# design.net
KiCad netlist of a schematic drawn in EasyEDA Pro
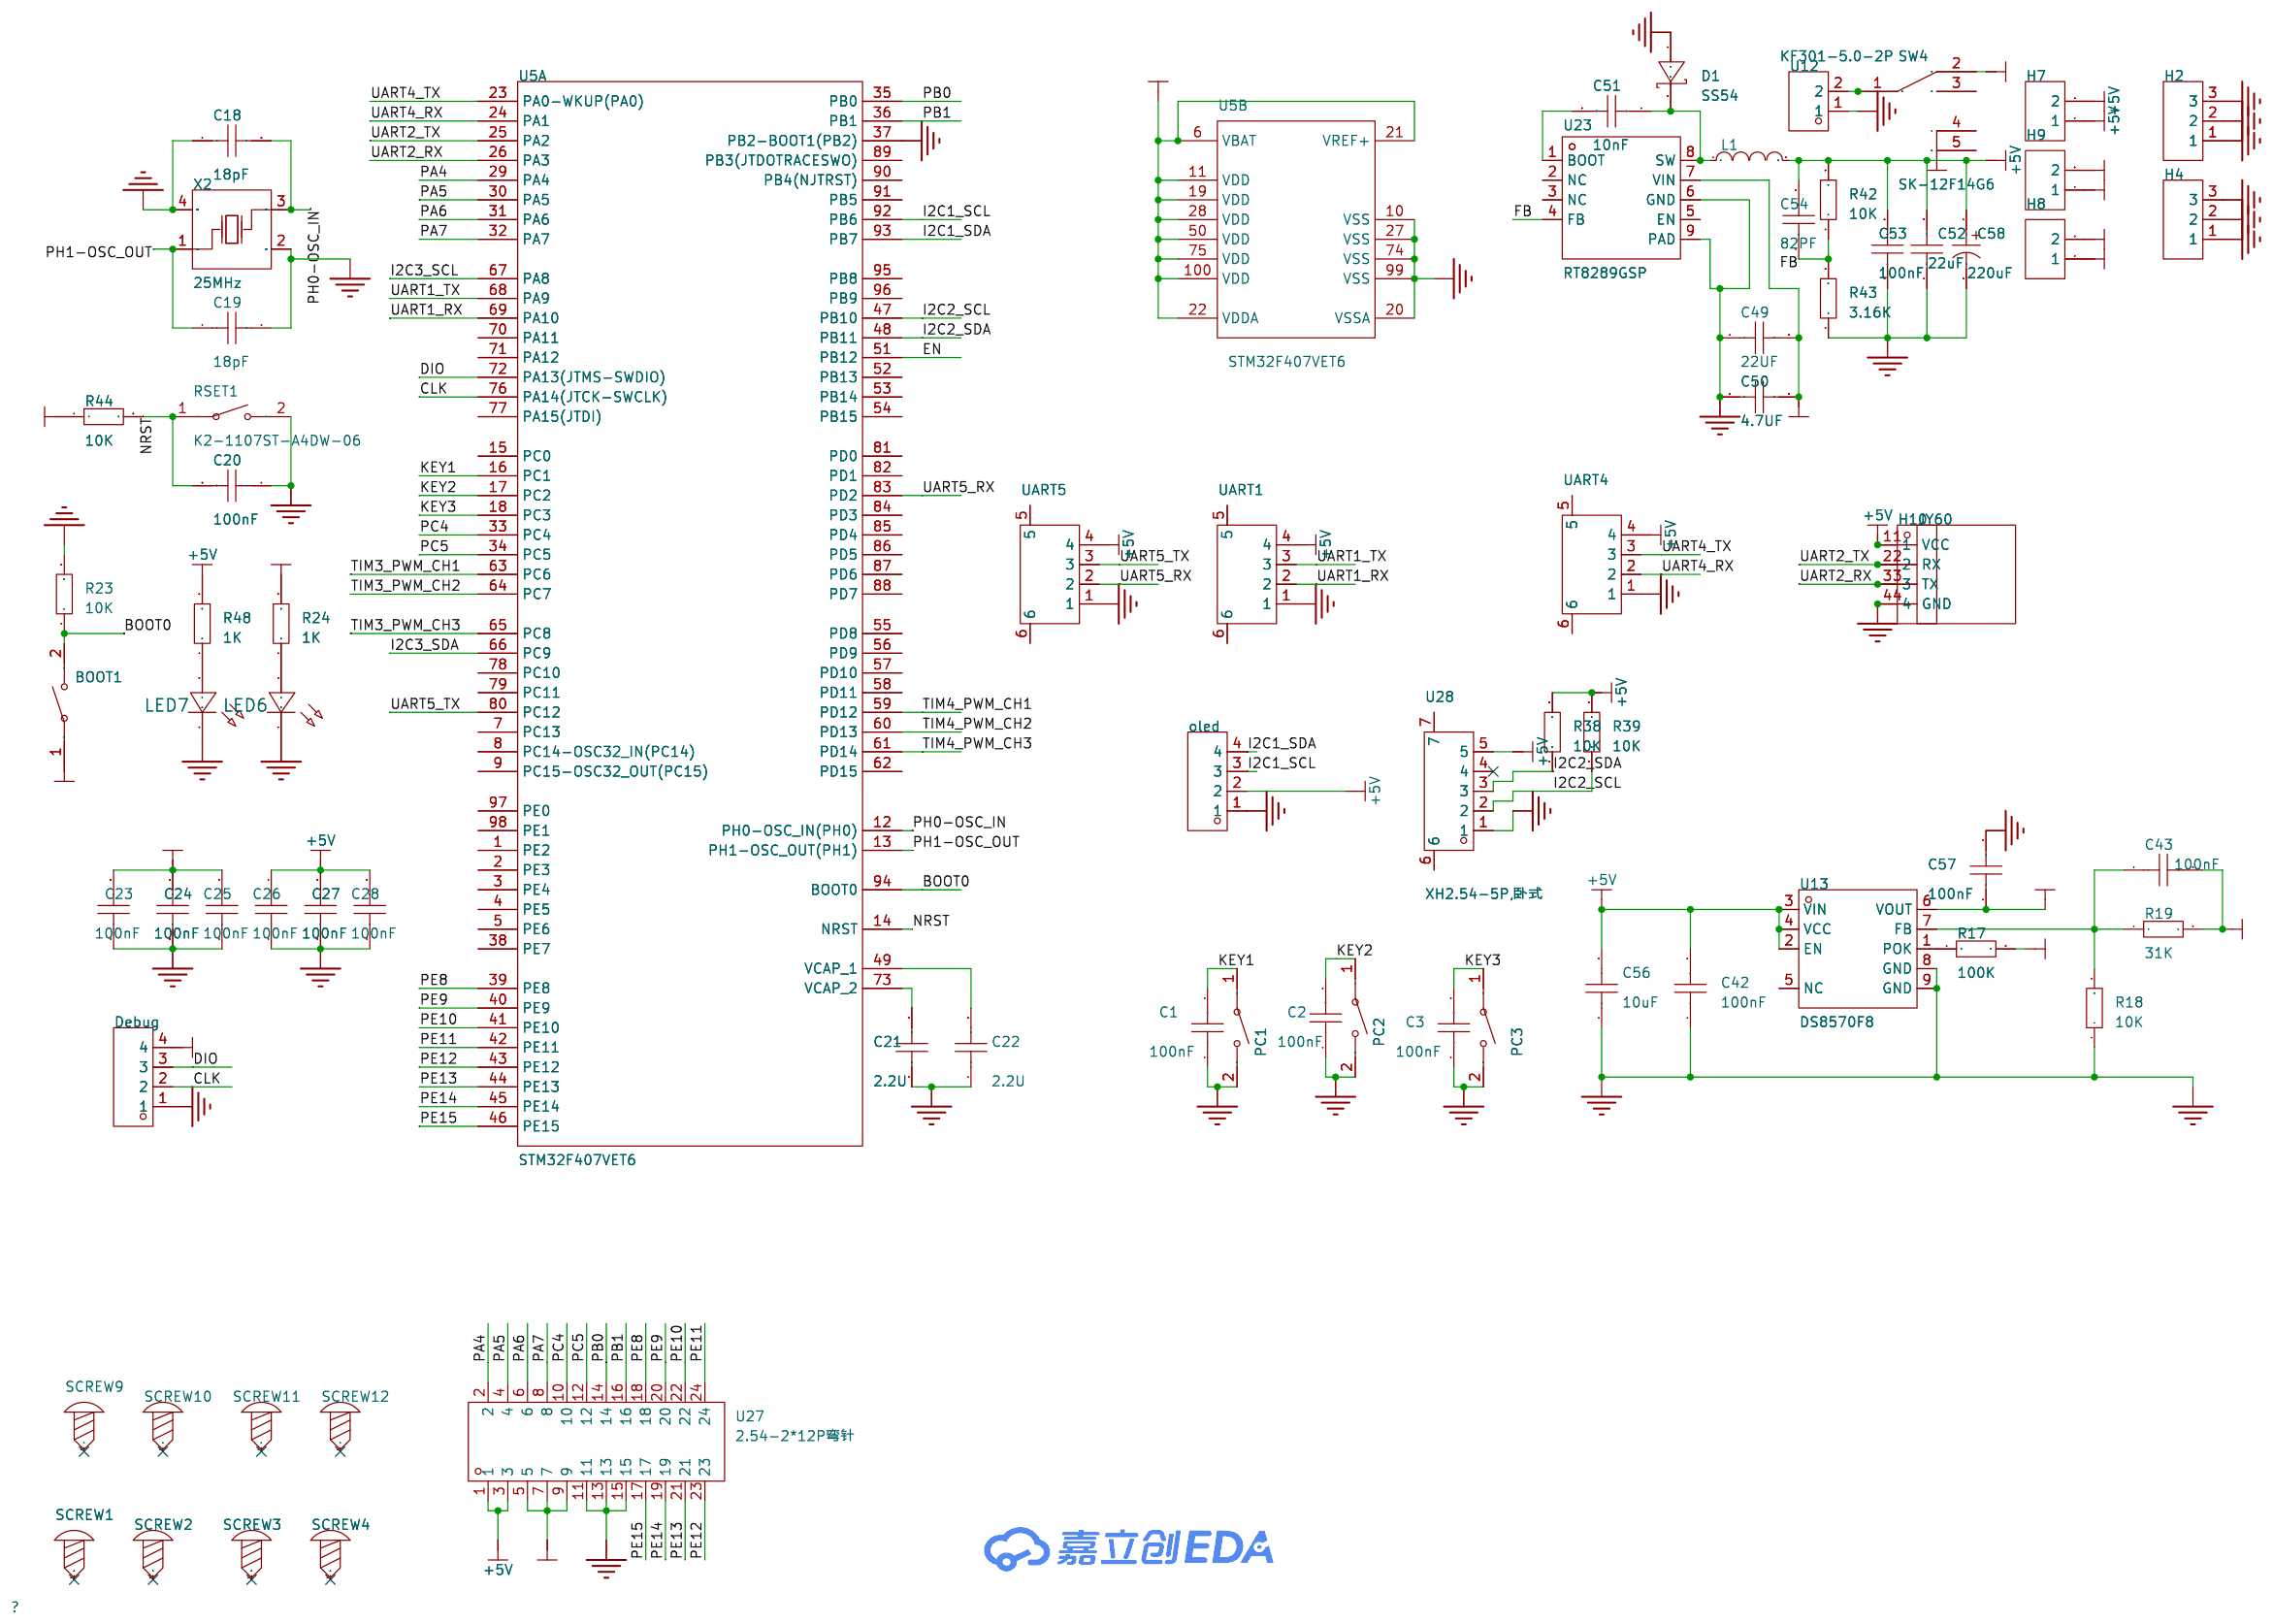
[diagram p0: 主控]
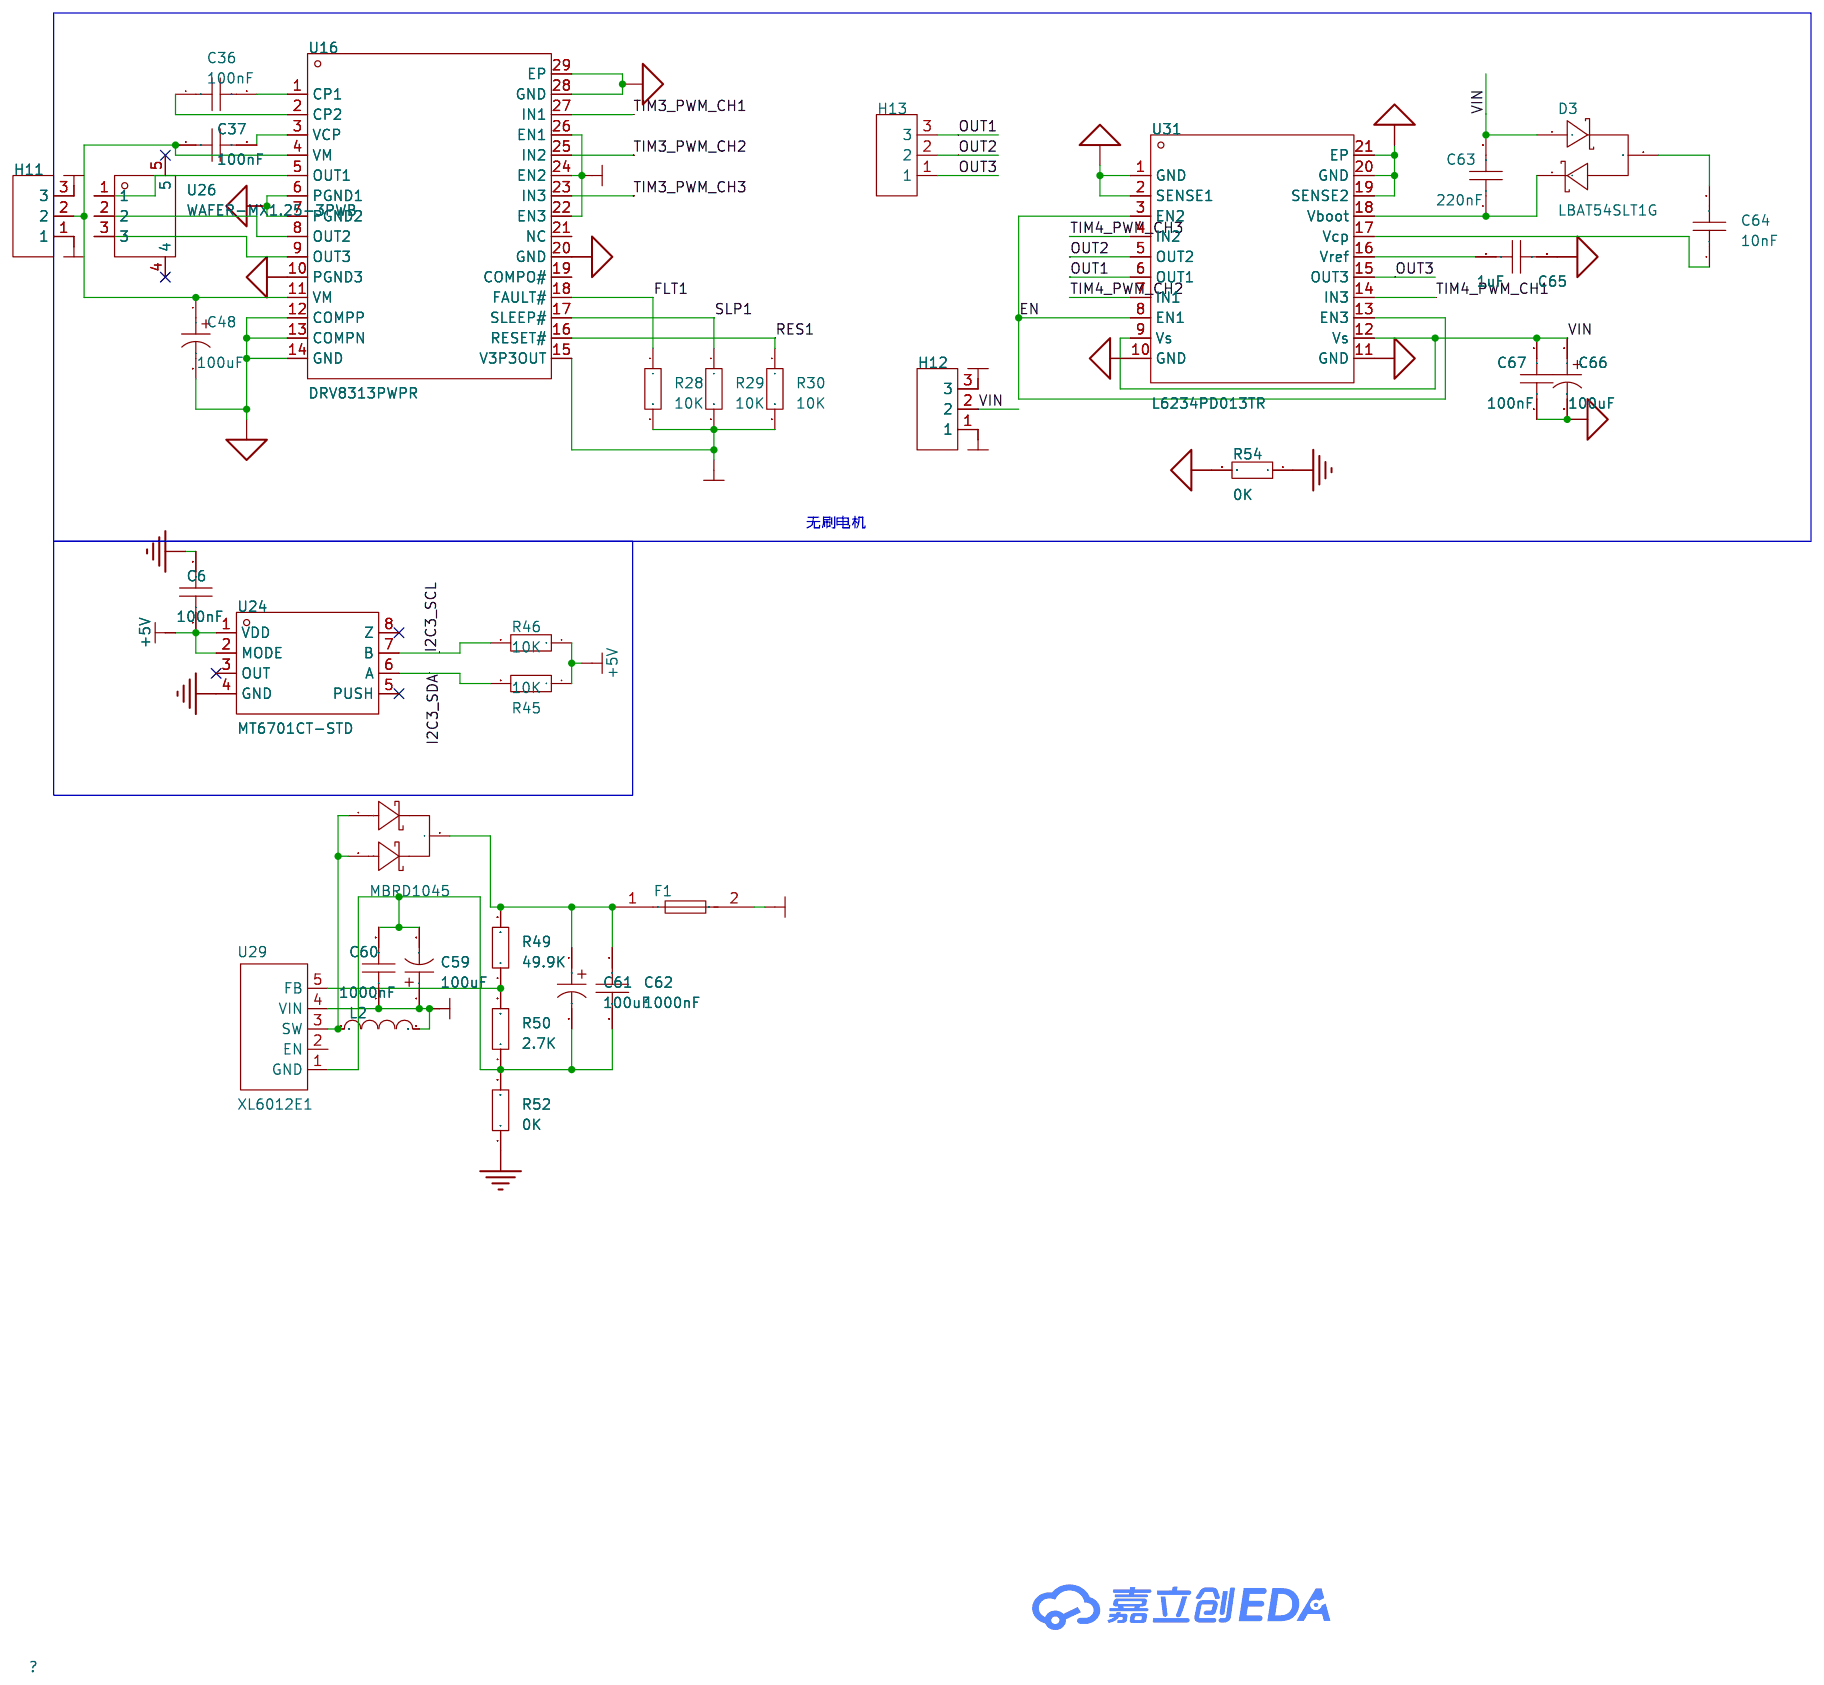
[diagram p1: 驱动]

(export (version "E")
  (design (tool "Eeschema 10.0.6"))
  (components
    (comp (ref "BOOT1")
      (value "K2-1107ST-A4DW-06")
      (footprint "easyedapro:KEY-SMD_L6.2-W3.6-LS8.0")
      (fields (field (name "Manufacturer") "韩国韩荣"))
      (libsource (lib "easyedapro") (part "K2-1107ST-A4SW-06"))
    )
    (comp (ref "C1")
      (value "100nF")
      (footprint "easyedapro:C0805")
      (libsource (lib "easyedapro") (part "CapAcitance"))
    )
    (comp (ref "C2")
      (value "100nF")
      (footprint "easyedapro:C0805")
      (libsource (lib "easyedapro") (part "CapAcitance"))
    )
    (comp (ref "C3")
      (value "100nF")
      (footprint "easyedapro:C0805")
      (libsource (lib "easyedapro") (part "CapAcitance"))
    )
    (comp (ref "C18")
      (value "18pF")
      (footprint "easyedapro:C0805")
      (libsource (lib "easyedapro") (part "CapAcitance"))
    )
    (comp (ref "C19")
      (value "18pF")
      (footprint "easyedapro:C0805")
      (libsource (lib "easyedapro") (part "CapAcitance"))
    )
    (comp (ref "C20")
      (value "100nF")
      (footprint "easyedapro:C0805")
      (libsource (lib "easyedapro") (part "CapAcitance"))
    )
    (comp (ref "C21")
      (value "2.2U")
      (footprint "easyedapro:C0805")
      (libsource (lib "easyedapro") (part "CapAcitance"))
    )
    (comp (ref "C22")
      (value "2.2U")
      (footprint "easyedapro:C0805")
      (libsource (lib "easyedapro") (part "CapAcitance"))
    )
    (comp (ref "C23")
      (value "100nF")
      (footprint "easyedapro:C0603")
      (libsource (lib "easyedapro") (part "CapAcitance"))
    )
    (comp (ref "C24")
      (value "100nF")
      (footprint "easyedapro:C0603")
      (libsource (lib "easyedapro") (part "CapAcitance"))
    )
    (comp (ref "C25")
      (value "100nF")
      (footprint "easyedapro:C0603")
      (libsource (lib "easyedapro") (part "CapAcitance"))
    )
    (comp (ref "C26")
      (value "100nF")
      (footprint "easyedapro:C0603")
      (libsource (lib "easyedapro") (part "CapAcitance"))
    )
    (comp (ref "C27")
      (value "100nF")
      (footprint "easyedapro:C0603")
      (libsource (lib "easyedapro") (part "CapAcitance"))
    )
    (comp (ref "C28")
      (value "100nF")
      (footprint "easyedapro:C0603")
      (libsource (lib "easyedapro") (part "CapAcitance"))
    )
    (comp (ref "C42")
      (value "100nF")
      (footprint "easyedapro:C0805")
      (libsource (lib "easyedapro") (part "CapAcitance"))
    )
    (comp (ref "C43")
      (value "100nF")
      (footprint "easyedapro:C0805")
      (libsource (lib "easyedapro") (part "CapAcitance"))
    )
    (comp (ref "C49")
      (value "22UF")
      (footprint "easyedapro:C0805")
      (libsource (lib "easyedapro") (part "CapAcitance"))
    )
    (comp (ref "C50")
      (value "4.7UF")
      (footprint "easyedapro:C0805")
      (libsource (lib "easyedapro") (part "CapAcitance"))
    )
    (comp (ref "C51")
      (value "10nF")
      (footprint "easyedapro:C0805")
      (libsource (lib "easyedapro") (part "CapAcitance"))
    )
    (comp (ref "C52")
      (value "22uF")
      (footprint "easyedapro:C0805")
      (libsource (lib "easyedapro") (part "CapAcitance"))
    )
    (comp (ref "C53")
      (value "100nF")
      (footprint "easyedapro:C0805")
      (libsource (lib "easyedapro") (part "CapAcitance"))
    )
    (comp (ref "C54")
      (value "82PF")
      (footprint "easyedapro:C0805")
      (libsource (lib "easyedapro") (part "CapAcitance"))
    )
    (comp (ref "C56")
      (value "10uF")
      (footprint "easyedapro:C0805")
      (libsource (lib "easyedapro") (part "CapAcitance"))
    )
    (comp (ref "C57")
      (value "100nF")
      (footprint "easyedapro:C0603")
      (libsource (lib "easyedapro") (part "CapAcitance"))
    )
    (comp (ref "C58")
      (value "220uF")
      (footprint "easyedapro:CAP-SMD_BD6.3-L6.6-W6.6-FD")
      (description "容值:100uF;精度:±20%;额定电压:35V;")
      (fields (field (name "Manufacturer Part") "VPXC0851V101MVTM") (field (name "Manufacturer") "Ymin(永铭)"))
      (libsource (lib "easyedapro") (part "VPXC0851V101MVTM"))
    )
    (comp (ref "D1")
      (value "SS54")
      (footprint "easyedapro:SMA_L4.4-W2.8-LS5.4-R-RD")
      (description "二极管配置:独立式;正向压降(Vf):550mV@5A;直流反向耐压(Vr):40V;整流电流:5A;")
      (fields (field (name "Manufacturer") "MDD(辰达半导体)"))
      (libsource (lib "easyedapro") (part "SS54_C22452"))
    )
    (comp (ref "Debug")
      (value "~")
      (footprint "easyedapro:HDR-TH_4P-P2.54-V-F")
      (libsource (lib "easyedapro") (part "2.54-1*4P母"))
    )
    (comp (ref "H2")
      (value "~")
      (footprint "easyedapro:HDR-TH_3P-P2.54-V-F")
      (libsource (lib "easyedapro") (part "PM254V-11-03-H85"))
    )
    (comp (ref "H4")
      (value "~")
      (footprint "easyedapro:HDR-TH_3P-P2.54-V-F")
      (libsource (lib "easyedapro") (part "PM254V-11-03-H85"))
    )
    (comp (ref "H7")
      (value "~")
      (footprint "easyedapro:HDR-TH_2P-P2.54-V-F")
      (libsource (lib "easyedapro") (part "Header-Female-2.54_1x2"))
    )
    (comp (ref "H8")
      (value "~")
      (footprint "easyedapro:HDR-TH_2P-P2.54-V-F")
      (libsource (lib "easyedapro") (part "Header-Female-2.54_1x2"))
    )
    (comp (ref "H9")
      (value "~")
      (footprint "easyedapro:HDR-TH_2P-P2.54-V-F")
      (libsource (lib "easyedapro") (part "Header-Female-2.54_1x2"))
    )
    (comp (ref "H10")
      (value "~")
      (footprint "easyedapro:HDR-TH_4P-P2.54-V-F")
      (libsource (lib "easyedapro") (part "2.54-1*4P母"))
    )
    (comp (ref "JY60") (value "~") (footprint "easyedapro:JY60") (libsource (lib "easyedapro") (part "JY60")))
    (comp (ref "L1")
      (value "APCI00121280150MB2-22uH")
      (footprint "easyedapro:IND-SMD_L12.0-W12.0_744771008")
      (libsource (lib "easyedapro") (part "APCI00121280150MB2-22UH"))
    )
    (comp (ref "LED6")
      (value "~")
      (footprint "easyedapro:LED_0805")
      (libsource (lib "easyedapro") (part "LED_R"))
    )
    (comp (ref "LED7")
      (value "~")
      (footprint "easyedapro:LED_0805")
      (libsource (lib "easyedapro") (part "LED_R"))
    )
    (comp (ref "oled")
      (value "~")
      (footprint "easyedapro:HDR-TH_4P-P2.54-V-F")
      (libsource (lib "easyedapro") (part "2.54-1*4P母"))
    )
    (comp (ref "PC1")
      (value "K2-1107ST-A4DW-06")
      (footprint "easyedapro:KEY-SMD_L6.2-W3.6-LS8.0")
      (fields (field (name "Manufacturer") "韩国韩荣"))
      (libsource (lib "easyedapro") (part "K2-1107ST-A4SW-06"))
    )
    (comp (ref "PC2")
      (value "K2-1107ST-A4DW-06")
      (footprint "easyedapro:KEY-SMD_L6.2-W3.6-LS8.0")
      (fields (field (name "Manufacturer") "韩国韩荣"))
      (libsource (lib "easyedapro") (part "K2-1107ST-A4SW-06"))
    )
    (comp (ref "PC3")
      (value "K2-1107ST-A4DW-06")
      (footprint "easyedapro:KEY-SMD_L6.2-W3.6-LS8.0")
      (fields (field (name "Manufacturer") "韩国韩荣"))
      (libsource (lib "easyedapro") (part "K2-1107ST-A4SW-06"))
    )
    (comp (ref "R17")
      (value "100K")
      (footprint "easyedapro:R0402")
      (libsource (lib "easyedapro") (part "电阻"))
    )
    (comp (ref "R18") (value "10K") (footprint "easyedapro:R0402") (libsource (lib "easyedapro") (part "电阻")))
    (comp (ref "R19") (value "31K") (footprint "easyedapro:R0402") (libsource (lib "easyedapro") (part "电阻")))
    (comp (ref "R23") (value "10K") (footprint "easyedapro:R0402") (libsource (lib "easyedapro") (part "电阻")))
    (comp (ref "R24") (value "1K") (footprint "easyedapro:R0402") (libsource (lib "easyedapro") (part "电阻")))
    (comp (ref "R38") (value "10K") (footprint "easyedapro:R0402") (libsource (lib "easyedapro") (part "电阻")))
    (comp (ref "R39") (value "10K") (footprint "easyedapro:R0402") (libsource (lib "easyedapro") (part "电阻")))
    (comp (ref "R42") (value "10K") (footprint "easyedapro:R0402") (libsource (lib "easyedapro") (part "电阻")))
    (comp (ref "R43")
      (value "3.16K")
      (footprint "easyedapro:R0402")
      (libsource (lib "easyedapro") (part "电阻"))
    )
    (comp (ref "R44") (value "10K") (footprint "easyedapro:R0402") (libsource (lib "easyedapro") (part "电阻")))
    (comp (ref "R48") (value "1K") (footprint "easyedapro:R0402") (libsource (lib "easyedapro") (part "电阻")))
    (comp (ref "RSET1")
      (value "K2-1107ST-A4DW-06")
      (footprint "easyedapro:KEY-SMD_L6.2-W3.6-LS8.0")
      (fields (field (name "Manufacturer") "韩国韩荣"))
      (libsource (lib "easyedapro") (part "K2-1107ST-A4SW-06"))
    )
    (comp (ref "SCREW1")
      (value "~")
      (footprint "easyedapro:M2螺丝")
      (libsource (lib "easyedapro") (part "螺丝孔"))
    )
    (comp (ref "SCREW2")
      (value "~")
      (footprint "easyedapro:M2螺丝")
      (libsource (lib "easyedapro") (part "螺丝孔"))
    )
    (comp (ref "SCREW3")
      (value "~")
      (footprint "easyedapro:M2螺丝")
      (libsource (lib "easyedapro") (part "螺丝孔"))
    )
    (comp (ref "SCREW4")
      (value "~")
      (footprint "easyedapro:M2螺丝")
      (libsource (lib "easyedapro") (part "螺丝孔"))
    )
    (comp (ref "SCREW9")
      (value "~")
      (footprint "easyedapro:M2螺丝")
      (libsource (lib "easyedapro") (part "螺丝孔"))
    )
    (comp (ref "SCREW10")
      (value "~")
      (footprint "easyedapro:M2螺丝")
      (libsource (lib "easyedapro") (part "螺丝孔"))
    )
    (comp (ref "SCREW11")
      (value "~")
      (footprint "easyedapro:M2螺丝")
      (libsource (lib "easyedapro") (part "螺丝孔"))
    )
    (comp (ref "SCREW12")
      (value "~")
      (footprint "easyedapro:M2螺丝")
      (libsource (lib "easyedapro") (part "螺丝孔"))
    )
    (comp (ref "SW4")
      (value "SK-12F14G6")
      (footprint "easyedapro:SW-TH_SK-12F14-G")
      (description "操作侧拨 插件卧式 尺寸中型 两档位")
      (fields (field (name "Manufacturer") "SOFNG(硕方)"))
      (libsource (lib "easyedapro") (part "SK-12F14G6"))
    )
    (comp (ref "U5")
      (value "STM32F407VET6")
      (footprint "easyedapro:LQFP-100_L14.0-W14.0-P0.50-LS16.0-BL")
      (description "CPU内核:ARM-M4;CPU最大主频:168MHz;应用领域:-;")
      (fields (field (name "Manufacturer") "ST(意法半导体)"))
      (libsource (lib "easyedapro") (part "STM32F407VET6"))
    )
    (comp (ref "U12")
      (value "KF301-5.0-2P")
      (footprint "easyedapro:CONN-TH_P5.00_KF301-5.0-2P")
      (fields (field (name "Manufacturer") "KEFA(科发)"))
      (libsource (lib "easyedapro") (part "KF301-5.0-2P"))
    )
    (comp (ref "U13")
      (value "DS8570F8")
      (footprint "easyedapro:ESOP-8_L4.9-W3.9-P1.27-LS6.0-BL-EP-1")
      (description "输出类型:可调;最大输入电压:-;输出电压:800mV~3.3V;最大输出电流:3A;输出极性:正极;")
      (fields (field (name "Manufacturer") "DSTECH(奥简科技)"))
      (libsource (lib "easyedapro") (part "DS8570F8"))
    )
    (comp (ref "U23")
      (value "RT8289GSP")
      (footprint "easyedapro:SOIC-8_L5.0-W4.0-P1.27-LS6.0-BL-EP2.0")
      (description "功能类型:降压型;输出类型:可调;工作电压:5.5V~32V;输出电压:1.222V~26V;输出电流:5A;")
      (fields (field (name "Manufacturer") "RICHTEK(立锜)"))
      (libsource (lib "easyedapro") (part "RT8289GSP"))
    )
    (comp (ref "U27")
      (value "2.54-2*12P弯针")
      (footprint "easyedapro:HDR-TH_24P-P2.54-H-M-R2-C12-S2.54")
      (fields (field (name "Manufacturer") "BOOMELE(博穆精密)"))
      (libsource (lib "easyedapro") (part "2.54-2*12P弯针"))
    )
    (comp (ref "U28")
      (value "XH2.54-5P,卧式")
      (footprint "easyedapro:CONN-SMD_5P-P2.50_XUNPU_WAFER-254W-5P")
      (libsource (lib "easyedapro") (part "XH2.54-5P,卧式"))
    )
    (comp (ref "UART1")
      (value "PH2.0-4P WT")
      (footprint "easyedapro:CONN-SMD_PH2.0-4PWB")
      (libsource (lib "easyedapro") (part "PH2.0-4P WT"))
    )
    (comp (ref "UART4")
      (value "PH2.0-4P WT")
      (footprint "easyedapro:CONN-SMD_PH2.0-4PWB")
      (libsource (lib "easyedapro") (part "PH2.0-4P WT"))
    )
    (comp (ref "UART5")
      (value "PH2.0-4P WT")
      (footprint "easyedapro:CONN-SMD_PH2.0-4PWB")
      (libsource (lib "easyedapro") (part "PH2.0-4P WT"))
    )
    (comp (ref "X2")
      (value "25MHz")
      (footprint "easyedapro:CRYSTAL-SMD_4P-L3.2-W2.5-BL")
      (description "晶振类型:贴片晶振;频率:25MHz;常温频差:±10ppm;负载电容:12pF;频率稳定度(全温):±20ppm;")
      (fields (field (name "Manufacturer Part") "X322525MOB4SI") (field (name "Manufacturer") "YXC(扬兴晶振)"))
      (libsource (lib "easyedapro") (part "X322525MOB4SI"))
    )
    (comp (ref "C6")
      (value "100nF")
      (footprint "easyedapro:C0603")
      (libsource (lib "easyedapro") (part "CapAcitance"))
    )
    (comp (ref "C36")
      (value "100nF")
      (footprint "easyedapro:C0603")
      (libsource (lib "easyedapro") (part "CapAcitance"))
    )
    (comp (ref "C37")
      (value "100nF")
      (footprint "easyedapro:C0603")
      (libsource (lib "easyedapro") (part "CapAcitance"))
    )
    (comp (ref "C48")
      (value "100uF")
      (footprint "easyedapro:CAP-SMD_BD6.3-L6.6-W6.6-FD")
      (description "容值:100uF;精度:±20%;额定电压:35V;")
      (fields (field (name "Manufacturer Part") "VPXC0851V101MVTM") (field (name "Manufacturer") "Ymin(永铭)"))
      (libsource (lib "easyedapro") (part "VPXC0851V101MVTM"))
    )
    (comp (ref "C59")
      (value "100uF")
      (footprint "easyedapro:CAP-SMD_BD6.3-L6.6-W6.6-FD")
      (description "容值:100uF;精度:±20%;额定电压:35V;")
      (fields (field (name "Manufacturer Part") "VPXC0851V101MVTM") (field (name "Manufacturer") "Ymin(永铭)"))
      (libsource (lib "easyedapro") (part "VPXC0851V101MVTM"))
    )
    (comp (ref "C60")
      (value "1000nF")
      (footprint "easyedapro:C0603")
      (libsource (lib "easyedapro") (part "CapAcitance"))
    )
    (comp (ref "C61")
      (value "100uF")
      (footprint "easyedapro:CAP-SMD_BD6.3-L6.6-W6.6-FD")
      (description "容值:100uF;精度:±20%;额定电压:35V;")
      (fields (field (name "Manufacturer Part") "VPXC0851V101MVTM") (field (name "Manufacturer") "Ymin(永铭)"))
      (libsource (lib "easyedapro") (part "VPXC0851V101MVTM"))
    )
    (comp (ref "C62")
      (value "1000nF")
      (footprint "easyedapro:C0603")
      (libsource (lib "easyedapro") (part "CapAcitance"))
    )
    (comp (ref "C63")
      (value "220nF")
      (footprint "easyedapro:C0805")
      (libsource (lib "easyedapro") (part "CapAcitance"))
    )
    (comp (ref "C64")
      (value "10nF")
      (footprint "easyedapro:C0805")
      (libsource (lib "easyedapro") (part "CapAcitance"))
    )
    (comp (ref "C65")
      (value "1uF")
      (footprint "easyedapro:C0805")
      (libsource (lib "easyedapro") (part "CapAcitance"))
    )
    (comp (ref "C66")
      (value "100uF")
      (footprint "easyedapro:CAP-SMD_BD6.3-L6.6-W6.6-FD")
      (description "容值:100uF;精度:±20%;额定电压:35V;")
      (fields (field (name "Manufacturer Part") "VPXC0851V101MVTM") (field (name "Manufacturer") "Ymin(永铭)"))
      (libsource (lib "easyedapro") (part "VPXC0851V101MVTM"))
    )
    (comp (ref "C67")
      (value "100nF")
      (footprint "easyedapro:C0805")
      (libsource (lib "easyedapro") (part "CapAcitance"))
    )
    (comp (ref "D2")
      (value "MBRD1045")
      (footprint "easyedapro:TO-252-3_L6.5-W5.9-P4.60-LS10.0-BL")
      (description "二极管配置:1对共阴极;正向压降(Vf):600mV@10A;直流反向耐压(Vr):45V;整流电流:10A;")
      (fields (field (name "Manufacturer") "GOODWORK(固得沃克)"))
      (libsource (lib "easyedapro") (part "MBRD1045"))
    )
    (comp (ref "D3")
      (value "LBAT54SLT1G")
      (footprint "easyedapro:SOT-23_L2.9-W1.3-P1.90-LS2.4-BR")
      (description "正向压降(Vf):400mV;直流反向耐压(Vr):30V;整流电流:200mA;")
      (fields (field (name "Manufacturer") "LRC(乐山无线电)"))
      (libsource (lib "easyedapro") (part "LBAT54SLT1G"))
    )
    (comp (ref "F1")
      (value "保险管座(插件),AC250V/10A,脚距23mm,配φ5")
      (footprint "easyedapro:FUSE-TH_L28.8-W10.0_C9900019320")
      (libsource (lib "easyedapro") (part "保险管座(插件),AC250V/10A,脚距23MM,配φ5"))
    )
    (comp (ref "H11")
      (value "~")
      (footprint "easyedapro:HDR-TH_3P-P2.54-V-F")
      (libsource (lib "easyedapro") (part "PM254V-11-03-H85"))
    )
    (comp (ref "H12")
      (value "~")
      (footprint "easyedapro:HDR-TH_3P-P2.54-V-F")
      (libsource (lib "easyedapro") (part "PM254V-11-03-H85"))
    )
    (comp (ref "H13")
      (value "~")
      (footprint "easyedapro:HDR-TH_3P-P2.54-V-F")
      (libsource (lib "easyedapro") (part "PM254V-11-03-H85"))
    )
    (comp (ref "L2")
      (value "APCI00121280150MB2-22uH")
      (footprint "easyedapro:IND-SMD_L12.0-W12.0_744771008")
      (libsource (lib "easyedapro") (part "APCI00121280150MB2-22UH"))
    )
    (comp (ref "R28") (value "10K") (footprint "easyedapro:R0402") (libsource (lib "easyedapro") (part "电阻")))
    (comp (ref "R29") (value "10K") (footprint "easyedapro:R0402") (libsource (lib "easyedapro") (part "电阻")))
    (comp (ref "R30") (value "10K") (footprint "easyedapro:R0402") (libsource (lib "easyedapro") (part "电阻")))
    (comp (ref "R45") (value "10K") (footprint "easyedapro:R0402") (libsource (lib "easyedapro") (part "电阻")))
    (comp (ref "R46") (value "10K") (footprint "easyedapro:R0402") (libsource (lib "easyedapro") (part "电阻")))
    (comp (ref "R49")
      (value "49.9K")
      (footprint "easyedapro:R0402")
      (libsource (lib "easyedapro") (part "电阻"))
    )
    (comp (ref "R50")
      (value "2.7K")
      (footprint "easyedapro:R0402")
      (libsource (lib "easyedapro") (part "电阻"))
    )
    (comp (ref "R52") (value "0K") (footprint "easyedapro:R0402") (libsource (lib "easyedapro") (part "电阻")))
    (comp (ref "R54") (value "0K") (footprint "easyedapro:R0402") (libsource (lib "easyedapro") (part "电阻")))
    (comp (ref "U16")
      (value "DRV8313PWPR")
      (footprint "easyedapro:HTSSOP-28_L9.8-W4.5-P0.65-LS6.6-BL-EP")
      (description "DRV8313 具有集成 FET、65V 最大电压、3A 峰值电流的三相电机驱动器")
      (fields (field (name "Manufacturer") "TI(德州仪器)"))
      (libsource (lib "easyedapro") (part "DRV8313PWPR"))
    )
    (comp (ref "U24")
      (value "MT6701CT-STD")
      (footprint "easyedapro:SOP-8_L4.9-W3.9-P1.27-LS6.0-BL")
      (description "磁性编码器 磁性编码开关 磁性角度检测IC 可编程磁性角度位置芯片")
      (fields (field (name "Manufacturer") "MagnTek(麦歌恩)"))
      (libsource (lib "easyedapro") (part "MT6701CT-STD"))
    )
    (comp (ref "U26")
      (value "WAFER-MX1.25-3PWB")
      (footprint "easyedapro:CONN-SMD_3P-P1.25_WAFER-MX1.25-3PWB")
      (fields (field (name "Manufacturer") "XUNPU(讯普)"))
      (libsource (lib "easyedapro") (part "WAFER-MX1.25-3PWB"))
    )
    (comp (ref "U29")
      (value "XL6012E1")
      (footprint "easyedapro:TO-220-5L_L10.2-W4.5-P1.71-L")
      (description "功能类型:升压型;输出类型:可调;工作电压:5V~40V;输出电压:-;输出电流:5A;")
      (fields (field (name "Manufacturer") "XLSEMI(芯龙)"))
      (libsource (lib "easyedapro") (part "XL6012E1"))
    )
    (comp (ref "U31")
      (value "L6234PD013TR")
      (footprint "easyedapro:POWERSO20_L15.9-W11.0-P1.27-LS14.2-BL-EP")
      (description "三相电机驱动器")
      (fields (field (name "Manufacturer") "ST(意法半导体)"))
      (libsource (lib "easyedapro") (part "L6234PD013TR"))
    )
  )
  (nets
    (net (code "1") (name "+3.3V") (class "Default")
      (node (ref "BOOT1") (pin "1") (pinfunction "1_1") (pintype "unspecified"))
      (node (ref "C23") (pin "2") (pinfunction "2_2") (pintype "input"))
      (node (ref "C24") (pin "2") (pinfunction "2_2") (pintype "input"))
      (node (ref "C25") (pin "2") (pinfunction "2_2") (pintype "input"))
      (node (ref "C43") (pin "2") (pinfunction "2_2") (pintype "input"))
      (node (ref "C57") (pin "1") (pinfunction "1_1") (pintype "input"))
      (node (ref "Debug") (pin "4") (pinfunction "4_4") (pintype "unspecified"))
      (node (ref "H9") (pin "1") (pinfunction "1_1") (pintype "input"))
      (node (ref "H9") (pin "2") (pinfunction "2_2") (pintype "input"))
      (node (ref "R17") (pin "2") (pinfunction "2_2") (pintype "input"))
      (node (ref "R19") (pin "2") (pinfunction "2_2") (pintype "input"))
      (node (ref "R24") (pin "2") (pinfunction "2_2") (pintype "input"))
      (node (ref "R28") (pin "2") (pinfunction "2_2") (pintype "input"))
      (node (ref "R29") (pin "2") (pinfunction "2_2") (pintype "input"))
      (node (ref "R30") (pin "2") (pinfunction "2_2") (pintype "input"))
      (node (ref "R44") (pin "1") (pinfunction "1_1") (pintype "input"))
      (node (ref "U13") (pin "6") (pinfunction "VOUT_6") (pintype "unspecified"))
      (node (ref "U16") (pin "15") (pinfunction "V3P3OUT_15") (pintype "unspecified"))
      (node (ref "U16") (pin "22") (pinfunction "EN3_22") (pintype "unspecified"))
      (node (ref "U16") (pin "24") (pinfunction "EN2_24") (pintype "unspecified"))
      (node (ref "U16") (pin "26") (pinfunction "EN1_26") (pintype "unspecified"))
      (node (ref "U27") (pin "5") (pinfunction "5_5") (pintype "unspecified"))
      (node (ref "U27") (pin "7") (pinfunction "7_7") (pintype "unspecified"))
      (node (ref "U27") (pin "9") (pinfunction "9_9") (pintype "unspecified"))
      (node (ref "U5") (pin "100") (pinfunction "VDD_100") (pintype "unspecified"))
      (node (ref "U5") (pin "11") (pinfunction "VDD_11") (pintype "unspecified"))
      (node (ref "U5") (pin "19") (pinfunction "VDD_19") (pintype "unspecified"))
      (node (ref "U5") (pin "21") (pinfunction "VREF+_21") (pintype "unspecified"))
      (node (ref "U5") (pin "22") (pinfunction "VDDA_22") (pintype "unspecified"))
      (node (ref "U5") (pin "28") (pinfunction "VDD_28") (pintype "unspecified"))
      (node (ref "U5") (pin "50") (pinfunction "VDD_50") (pintype "unspecified"))
      (node (ref "U5") (pin "6") (pinfunction "VBAT_6") (pintype "unspecified"))
      (node (ref "U5") (pin "75") (pinfunction "VDD_75") (pintype "unspecified"))
    )
    (net (code "2") (name "+5V") (class "Default")
      (node (ref "C26") (pin "2") (pinfunction "2_2") (pintype "input"))
      (node (ref "C27") (pin "2") (pinfunction "2_2") (pintype "input"))
      (node (ref "C28") (pin "2") (pinfunction "2_2") (pintype "input"))
      (node (ref "C42") (pin "2") (pinfunction "2_2") (pintype "input"))
      (node (ref "C52") (pin "2") (pinfunction "2_2") (pintype "input"))
      (node (ref "C53") (pin "2") (pinfunction "2_2") (pintype "input"))
      (node (ref "C54") (pin "2") (pinfunction "2_2") (pintype "input"))
      (node (ref "C56") (pin "2") (pinfunction "2_2") (pintype "input"))
      (node (ref "C58") (pin "1") (pinfunction "1_1") (pintype "input"))
      (node (ref "C6") (pin "1") (pinfunction "1_1") (pintype "input"))
      (node (ref "H10") (pin "1") (pinfunction "1_1") (pintype "unspecified"))
      (node (ref "H7") (pin "1") (pinfunction "1_1") (pintype "input"))
      (node (ref "H7") (pin "2") (pinfunction "2_2") (pintype "input"))
      (node (ref "JY60") (pin "1") (pinfunction "VCC_1") (pintype "input"))
      (node (ref "L1") (pin "2") (pinfunction "2_2") (pintype "unspecified"))
      (node (ref "R38") (pin "2") (pinfunction "2_2") (pintype "input"))
      (node (ref "R39") (pin "2") (pinfunction "2_2") (pintype "input"))
      (node (ref "R42") (pin "2") (pinfunction "2_2") (pintype "input"))
      (node (ref "R45") (pin "1") (pinfunction "1_1") (pintype "input"))
      (node (ref "R46") (pin "1") (pinfunction "1_1") (pintype "input"))
      (node (ref "R48") (pin "2") (pinfunction "2_2") (pintype "input"))
      (node (ref "U13") (pin "2") (pinfunction "EN_2") (pintype "unspecified"))
      (node (ref "U13") (pin "3") (pinfunction "VIN_3") (pintype "unspecified"))
      (node (ref "U13") (pin "4") (pinfunction "VCC_4") (pintype "unspecified"))
      (node (ref "U24") (pin "1") (pinfunction "VDD_1") (pintype "unspecified"))
      (node (ref "U24") (pin "2") (pinfunction "MODE_2") (pintype "unspecified"))
      (node (ref "U27") (pin "1") (pinfunction "1_1") (pintype "unspecified"))
      (node (ref "U27") (pin "3") (pinfunction "3_3") (pintype "unspecified"))
      (node (ref "U28") (pin "5") (pinfunction "5_5") (pintype "unspecified"))
      (node (ref "UART1") (pin "4") (pinfunction "4_4") (pintype "unspecified"))
      (node (ref "UART4") (pin "4") (pinfunction "4_4") (pintype "unspecified"))
      (node (ref "UART5") (pin "4") (pinfunction "4_4") (pintype "unspecified"))
      (node (ref "oled") (pin "2") (pinfunction "2_2") (pintype "unspecified"))
    )
    (net (code "3") (name "+12V") (class "Default")
      (node (ref "C49") (pin "2") (pinfunction "2_2") (pintype "input"))
      (node (ref "C50") (pin "2") (pinfunction "2_2") (pintype "input"))
      (node (ref "C59") (pin "1") (pinfunction "1_1") (pintype "input"))
      (node (ref "C60") (pin "1") (pinfunction "1_1") (pintype "input"))
      (node (ref "H11") (pin "3") (pinfunction "3_3") (pintype "unspecified"))
      (node (ref "H12") (pin "3") (pinfunction "3_3") (pintype "unspecified"))
      (node (ref "H8") (pin "1") (pinfunction "1_1") (pintype "input"))
      (node (ref "H8") (pin "2") (pinfunction "2_2") (pintype "input"))
      (node (ref "L2") (pin "2") (pinfunction "2_2") (pintype "unspecified"))
      (node (ref "SW4") (pin "2") (pinfunction "2_2") (pintype "unspecified"))
      (node (ref "U23") (pin "7") (pinfunction "VIN_7") (pintype "unspecified"))
      (node (ref "U29") (pin "4") (pinfunction "VIN_4") (pintype "unspecified"))
    )
    (net (code "4") (name "+24V") (class "Default")
      (node (ref "F1") (pin "2") (pinfunction "2_2") (pintype "unspecified"))
      (node (ref "H11") (pin "1") (pinfunction "1_1") (pintype "unspecified"))
      (node (ref "H12") (pin "1") (pinfunction "1_1") (pintype "unspecified"))
    )
    (net (code "5") (name "AGND") (class "Default")
      (node (ref "C48") (pin "2") (pinfunction "2_2") (pintype "input"))
      (node (ref "C65") (pin "2") (pinfunction "2_2") (pintype "input"))
      (node (ref "C66") (pin "2") (pinfunction "2_2") (pintype "input"))
      (node (ref "C67") (pin "1") (pinfunction "1_1") (pintype "input"))
      (node (ref "R54") (pin "2") (pinfunction "2_2") (pintype "input"))
      (node (ref "U16") (pin "10") (pinfunction "PGND3_10") (pintype "unspecified"))
      (node (ref "U16") (pin "12") (pinfunction "COMPP_12") (pintype "unspecified"))
      (node (ref "U16") (pin "13") (pinfunction "COMPN_13") (pintype "unspecified"))
      (node (ref "U16") (pin "14") (pinfunction "GND_14") (pintype "unspecified"))
      (node (ref "U16") (pin "20") (pinfunction "GND_20") (pintype "unspecified"))
      (node (ref "U16") (pin "28") (pinfunction "GND_28") (pintype "unspecified"))
      (node (ref "U16") (pin "29") (pinfunction "EP_29") (pintype "unspecified"))
      (node (ref "U16") (pin "6") (pinfunction "PGND1_6") (pintype "unspecified"))
      (node (ref "U16") (pin "7") (pinfunction "PGND2_7") (pintype "unspecified"))
      (node (ref "U31") (pin "1") (pinfunction "GND_1") (pintype "unspecified"))
      (node (ref "U31") (pin "10") (pinfunction "GND_10") (pintype "unspecified"))
      (node (ref "U31") (pin "11") (pinfunction "GND_11") (pintype "unspecified"))
      (node (ref "U31") (pin "19") (pinfunction "SENSE2_19") (pintype "unspecified"))
      (node (ref "U31") (pin "2") (pinfunction "SENSE1_2") (pintype "unspecified"))
      (node (ref "U31") (pin "20") (pinfunction "GND_20") (pintype "unspecified"))
      (node (ref "U31") (pin "21") (pinfunction "EP_21") (pintype "unspecified"))
    )
    (net (code "6") (name "BOOT0") (class "Default")
      (node (ref "BOOT1") (pin "2") (pinfunction "2_2") (pintype "unspecified"))
      (node (ref "R23") (pin "1") (pinfunction "1_1") (pintype "input"))
      (node (ref "U5") (pin "94") (pinfunction "BOOT0_94") (pintype "unspecified"))
    )
    (net (code "7") (name "CLK") (class "Default")
      (node (ref "Debug") (pin "2") (pinfunction "2_2") (pintype "unspecified"))
      (node (ref "U5") (pin "76") (pinfunction "PA14(JTCK-SWCLK)_76") (pintype "bidirectional"))
    )
    (net (code "8") (name "DIO") (class "Default")
      (node (ref "Debug") (pin "3") (pinfunction "3_3") (pintype "unspecified"))
      (node (ref "U5") (pin "72") (pinfunction "PA13(JTMS-SWDIO)_72") (pintype "bidirectional"))
    )
    (net (code "9") (name "EN") (class "Default")
      (node (ref "U31") (pin "13") (pinfunction "EN3_13") (pintype "unspecified"))
      (node (ref "U31") (pin "3") (pinfunction "EN2_3") (pintype "unspecified"))
      (node (ref "U31") (pin "8") (pinfunction "EN1_8") (pintype "unspecified"))
      (node (ref "U5") (pin "51") (pinfunction "PB12_51") (pintype "bidirectional"))
    )
    (net (code "10") (name "FB") (class "Default")
      (node (ref "C54") (pin "1") (pinfunction "1_1") (pintype "input"))
      (node (ref "R42") (pin "1") (pinfunction "1_1") (pintype "input"))
      (node (ref "R43") (pin "2") (pinfunction "2_2") (pintype "input"))
      (node (ref "U23") (pin "4") (pinfunction "FB_4") (pintype "unspecified"))
    )
    (net (code "11") (name "FLT1") (class "Default")
      (node (ref "R28") (pin "1") (pinfunction "1_1") (pintype "input"))
      (node (ref "U16") (pin "18") (pinfunction "FAULT#_18") (pintype "unspecified"))
    )
    (net (code "12") (name "GND") (class "Default")
      (node (ref "C1") (pin "1") (pinfunction "1_1") (pintype "input"))
      (node (ref "C18") (pin "1") (pinfunction "1_1") (pintype "input"))
      (node (ref "C19") (pin "2") (pinfunction "2_2") (pintype "input"))
      (node (ref "C2") (pin "1") (pinfunction "1_1") (pintype "input"))
      (node (ref "C20") (pin "1") (pinfunction "1_1") (pintype "input"))
      (node (ref "C21") (pin "1") (pinfunction "1_1") (pintype "input"))
      (node (ref "C22") (pin "1") (pinfunction "1_1") (pintype "input"))
      (node (ref "C23") (pin "1") (pinfunction "1_1") (pintype "input"))
      (node (ref "C24") (pin "1") (pinfunction "1_1") (pintype "input"))
      (node (ref "C25") (pin "1") (pinfunction "1_1") (pintype "input"))
      (node (ref "C26") (pin "1") (pinfunction "1_1") (pintype "input"))
      (node (ref "C27") (pin "1") (pinfunction "1_1") (pintype "input"))
      (node (ref "C28") (pin "1") (pinfunction "1_1") (pintype "input"))
      (node (ref "C3") (pin "1") (pinfunction "1_1") (pintype "input"))
      (node (ref "C42") (pin "1") (pinfunction "1_1") (pintype "input"))
      (node (ref "C49") (pin "1") (pinfunction "1_1") (pintype "input"))
      (node (ref "C50") (pin "1") (pinfunction "1_1") (pintype "input"))
      (node (ref "C52") (pin "1") (pinfunction "1_1") (pintype "input"))
      (node (ref "C53") (pin "1") (pinfunction "1_1") (pintype "input"))
      (node (ref "C56") (pin "1") (pinfunction "1_1") (pintype "input"))
      (node (ref "C57") (pin "2") (pinfunction "2_2") (pintype "input"))
      (node (ref "C58") (pin "2") (pinfunction "2_2") (pintype "input"))
      (node (ref "C6") (pin "2") (pinfunction "2_2") (pintype "input"))
      (node (ref "D1") (pin "1") (pinfunction "A_1") (pintype "unspecified"))
      (node (ref "Debug") (pin "1") (pinfunction "1_1") (pintype "unspecified"))
      (node (ref "H10") (pin "4") (pinfunction "4_4") (pintype "unspecified"))
      (node (ref "H2") (pin "1") (pinfunction "1_1") (pintype "unspecified"))
      (node (ref "H2") (pin "2") (pinfunction "2_2") (pintype "unspecified"))
      (node (ref "H2") (pin "3") (pinfunction "3_3") (pintype "unspecified"))
      (node (ref "H4") (pin "1") (pinfunction "1_1") (pintype "unspecified"))
      (node (ref "H4") (pin "2") (pinfunction "2_2") (pintype "unspecified"))
      (node (ref "H4") (pin "3") (pinfunction "3_3") (pintype "unspecified"))
      (node (ref "JY60") (pin "4") (pinfunction "GND_4") (pintype "input"))
      (node (ref "LED6") (pin "1") (pinfunction "C_1") (pintype "input"))
      (node (ref "LED7") (pin "1") (pinfunction "C_1") (pintype "input"))
      (node (ref "PC1") (pin "2") (pinfunction "2_2") (pintype "unspecified"))
      (node (ref "PC2") (pin "2") (pinfunction "2_2") (pintype "unspecified"))
      (node (ref "PC3") (pin "2") (pinfunction "2_2") (pintype "unspecified"))
      (node (ref "R18") (pin "1") (pinfunction "1_1") (pintype "input"))
      (node (ref "R23") (pin "2") (pinfunction "2_2") (pintype "input"))
      (node (ref "R43") (pin "1") (pinfunction "1_1") (pintype "input"))
      (node (ref "R52") (pin "1") (pinfunction "1_1") (pintype "input"))
      (node (ref "R54") (pin "1") (pinfunction "1_1") (pintype "input"))
      (node (ref "RSET1") (pin "2") (pinfunction "2_2") (pintype "unspecified"))
      (node (ref "U12") (pin "1") (pinfunction "1_1") (pintype "unspecified"))
      (node (ref "U13") (pin "8") (pinfunction "GND_8") (pintype "unspecified"))
      (node (ref "U13") (pin "9") (pinfunction "GND_9") (pintype "unspecified"))
      (node (ref "U23") (pin "6") (pinfunction "GND_6") (pintype "unspecified"))
      (node (ref "U23") (pin "9") (pinfunction "PAD_9") (pintype "unspecified"))
      (node (ref "U24") (pin "4") (pinfunction "GND_4") (pintype "unspecified"))
      (node (ref "U27") (pin "11") (pinfunction "11_11") (pintype "unspecified"))
      (node (ref "U27") (pin "13") (pinfunction "13_13") (pintype "unspecified"))
      (node (ref "U27") (pin "15") (pinfunction "15_15") (pintype "unspecified"))
      (node (ref "U28") (pin "1") (pinfunction "1_1") (pintype "unspecified"))
      (node (ref "U5") (pin "10") (pinfunction "VSS_10") (pintype "unspecified"))
      (node (ref "U5") (pin "20") (pinfunction "VSSA_20") (pintype "unspecified"))
      (node (ref "U5") (pin "27") (pinfunction "VSS_27") (pintype "unspecified"))
      (node (ref "U5") (pin "37") (pinfunction "PB2-BOOT1(PB2)_37") (pintype "bidirectional"))
      (node (ref "U5") (pin "74") (pinfunction "VSS_74") (pintype "unspecified"))
      (node (ref "U5") (pin "99") (pinfunction "VSS_99") (pintype "unspecified"))
      (node (ref "UART1") (pin "1") (pinfunction "1_1") (pintype "unspecified"))
      (node (ref "UART4") (pin "1") (pinfunction "1_1") (pintype "unspecified"))
      (node (ref "UART5") (pin "1") (pinfunction "1_1") (pintype "unspecified"))
      (node (ref "X2") (pin "2") (pinfunction "GND_2") (pintype "unspecified"))
      (node (ref "X2") (pin "4") (pinfunction "GND_4") (pintype "unspecified"))
      (node (ref "oled") (pin "1") (pinfunction "1_1") (pintype "unspecified"))
    )
    (net (code "13") (name "I2C1_SCL") (class "Default")
      (node (ref "U5") (pin "92") (pinfunction "PB6_92") (pintype "bidirectional"))
      (node (ref "oled") (pin "3") (pinfunction "3_3") (pintype "unspecified"))
    )
    (net (code "14") (name "I2C1_SDA") (class "Default")
      (node (ref "U5") (pin "93") (pinfunction "PB7_93") (pintype "bidirectional"))
      (node (ref "oled") (pin "4") (pinfunction "4_4") (pintype "unspecified"))
    )
    (net (code "15") (name "I2C2_SCL") (class "Default")
      (node (ref "R39") (pin "1") (pinfunction "1_1") (pintype "input"))
      (node (ref "U28") (pin "2") (pinfunction "2_2") (pintype "unspecified"))
      (node (ref "U5") (pin "47") (pinfunction "PB10_47") (pintype "bidirectional"))
    )
    (net (code "16") (name "I2C2_SDA") (class "Default")
      (node (ref "R38") (pin "1") (pinfunction "1_1") (pintype "input"))
      (node (ref "U28") (pin "3") (pinfunction "3_3") (pintype "unspecified"))
      (node (ref "U5") (pin "48") (pinfunction "PB11_48") (pintype "bidirectional"))
    )
    (net (code "17") (name "I2C3_SCL") (class "Default")
      (node (ref "R46") (pin "2") (pinfunction "2_2") (pintype "input"))
      (node (ref "U24") (pin "7") (pinfunction "B_7") (pintype "unspecified"))
      (node (ref "U5") (pin "67") (pinfunction "PA8_67") (pintype "bidirectional"))
    )
    (net (code "18") (name "I2C3_SDA") (class "Default")
      (node (ref "R45") (pin "2") (pinfunction "2_2") (pintype "input"))
      (node (ref "U24") (pin "6") (pinfunction "A_6") (pintype "unspecified"))
      (node (ref "U5") (pin "66") (pinfunction "PC9_66") (pintype "bidirectional"))
    )
    (net (code "19") (name "KEY1") (class "Default")
      (node (ref "C1") (pin "2") (pinfunction "2_2") (pintype "input"))
      (node (ref "PC1") (pin "1") (pinfunction "1_1") (pintype "unspecified"))
      (node (ref "U5") (pin "16") (pinfunction "PC1_16") (pintype "bidirectional"))
    )
    (net (code "20") (name "KEY2") (class "Default")
      (node (ref "C2") (pin "2") (pinfunction "2_2") (pintype "input"))
      (node (ref "PC2") (pin "1") (pinfunction "1_1") (pintype "unspecified"))
      (node (ref "U5") (pin "17") (pinfunction "PC2_17") (pintype "bidirectional"))
    )
    (net (code "21") (name "KEY3") (class "Default")
      (node (ref "C3") (pin "2") (pinfunction "2_2") (pintype "input"))
      (node (ref "PC3") (pin "1") (pinfunction "1_1") (pintype "unspecified"))
      (node (ref "U5") (pin "18") (pinfunction "PC3_18") (pintype "bidirectional"))
    )
    (net (code "22") (name "NRST") (class "Default")
      (node (ref "C20") (pin "2") (pinfunction "2_2") (pintype "input"))
      (node (ref "R44") (pin "2") (pinfunction "2_2") (pintype "input"))
      (node (ref "RSET1") (pin "1") (pinfunction "1_1") (pintype "unspecified"))
      (node (ref "U5") (pin "14") (pinfunction "NRST_14") (pintype "bidirectional"))
    )
    (net (code "23") (name "Net-(C37-Pad1)") (class "Default")
      (node (ref "C37") (pin "1") (pinfunction "1_1") (pintype "input"))
      (node (ref "C48") (pin "1") (pinfunction "1_1") (pintype "input"))
      (node (ref "H11") (pin "2") (pinfunction "2_2") (pintype "unspecified"))
      (node (ref "U16") (pin "11") (pinfunction "VM_11") (pintype "unspecified"))
      (node (ref "U16") (pin "4") (pinfunction "VM_4") (pintype "unspecified"))
    )
    (net (code "24") (name "Net-(D1-K)") (class "Default")
      (node (ref "C51") (pin "1") (pinfunction "1_1") (pintype "input"))
      (node (ref "D1") (pin "2") (pinfunction "K_2") (pintype "unspecified"))
      (node (ref "L1") (pin "1") (pinfunction "1_1") (pintype "unspecified"))
      (node (ref "U23") (pin "8") (pinfunction "SW_8") (pintype "unspecified"))
    )
    (net (code "25") (name "Net-(D2-K)") (class "Default")
      (node (ref "C61") (pin "1") (pinfunction "1_1") (pintype "input"))
      (node (ref "C62") (pin "1") (pinfunction "1_1") (pintype "input"))
      (node (ref "D2") (pin "2") (pinfunction "K_2") (pintype "unspecified"))
      (node (ref "F1") (pin "1") (pinfunction "1_1") (pintype "unspecified"))
      (node (ref "R49") (pin "2") (pinfunction "2_2") (pintype "input"))
    )
    (net (code "26") (name "Net-(D3-AK)") (class "Default")
      (node (ref "C64") (pin "2") (pinfunction "2_2") (pintype "input"))
      (node (ref "D3") (pin "3") (pinfunction "AK_3") (pintype "unspecified"))
    )
    (net (code "27") (name "Net-(D3-K)") (class "Default")
      (node (ref "C63") (pin "1") (pinfunction "1_1") (pintype "input"))
      (node (ref "D3") (pin "2") (pinfunction "K_2") (pintype "unspecified"))
      (node (ref "U31") (pin "18") (pinfunction "Vboot_18") (pintype "unspecified"))
    )
    (net (code "28") (name "Net-(LED6-A)") (class "Default")
      (node (ref "LED6") (pin "2") (pinfunction "A_2") (pintype "input"))
      (node (ref "R24") (pin "1") (pinfunction "1_1") (pintype "input"))
    )
    (net (code "29") (name "Net-(LED7-A)") (class "Default")
      (node (ref "LED7") (pin "2") (pinfunction "A_2") (pintype "input"))
      (node (ref "R48") (pin "1") (pinfunction "1_1") (pintype "input"))
    )
    (net (code "30") (name "Net-(SW4-Pad1)") (class "Default")
      (node (ref "SW4") (pin "1") (pinfunction "1_1") (pintype "unspecified"))
      (node (ref "U12") (pin "2") (pinfunction "2_2") (pintype "unspecified"))
    )
    (net (code "31") (name "Net-(U5A-VCAP_1)") (class "Default")
      (node (ref "C22") (pin "2") (pinfunction "2_2") (pintype "input"))
      (node (ref "U5") (pin "49") (pinfunction "VCAP_1_49") (pintype "unspecified"))
    )
    (net (code "32") (name "Net-(U5A-VCAP_2)") (class "Default")
      (node (ref "C21") (pin "2") (pinfunction "2_2") (pintype "input"))
      (node (ref "U5") (pin "73") (pinfunction "VCAP_2_73") (pintype "unspecified"))
    )
    (net (code "33") (name "Net-(U13-FB)") (class "Default")
      (node (ref "C43") (pin "1") (pinfunction "1_1") (pintype "input"))
      (node (ref "R18") (pin "2") (pinfunction "2_2") (pintype "input"))
      (node (ref "R19") (pin "1") (pinfunction "1_1") (pintype "input"))
      (node (ref "U13") (pin "7") (pinfunction "FB_7") (pintype "unspecified"))
    )
    (net (code "34") (name "Net-(U13-POK)") (class "Default")
      (node (ref "R17") (pin "1") (pinfunction "1_1") (pintype "input"))
      (node (ref "U13") (pin "1") (pinfunction "POK_1") (pintype "unspecified"))
    )
    (net (code "35") (name "Net-(U16-CP1)") (class "Default")
      (node (ref "C36") (pin "2") (pinfunction "2_2") (pintype "input"))
      (node (ref "U16") (pin "1") (pinfunction "CP1_1") (pintype "unspecified"))
    )
    (net (code "36") (name "Net-(U16-CP2)") (class "Default")
      (node (ref "C36") (pin "1") (pinfunction "1_1") (pintype "input"))
      (node (ref "U16") (pin "2") (pinfunction "CP2_2") (pintype "unspecified"))
    )
    (net (code "37") (name "Net-(U16-OUT1)") (class "Default")
      (node (ref "U16") (pin "5") (pinfunction "OUT1_5") (pintype "unspecified"))
      (node (ref "U26") (pin "1") (pinfunction "1_1") (pintype "unspecified"))
    )
    (net (code "38") (name "Net-(U16-OUT2)") (class "Default")
      (node (ref "U16") (pin "8") (pinfunction "OUT2_8") (pintype "unspecified"))
      (node (ref "U26") (pin "2") (pinfunction "2_2") (pintype "unspecified"))
    )
    (net (code "39") (name "Net-(U16-OUT3)") (class "Default")
      (node (ref "U16") (pin "9") (pinfunction "OUT3_9") (pintype "unspecified"))
      (node (ref "U26") (pin "3") (pinfunction "3_3") (pintype "unspecified"))
    )
    (net (code "40") (name "Net-(U16-VCP)") (class "Default")
      (node (ref "C37") (pin "2") (pinfunction "2_2") (pintype "input"))
      (node (ref "U16") (pin "3") (pinfunction "VCP_3") (pintype "unspecified"))
    )
    (net (code "41") (name "Net-(U23-BOOT)") (class "Default")
      (node (ref "C51") (pin "2") (pinfunction "2_2") (pintype "input"))
      (node (ref "U23") (pin "1") (pinfunction "BOOT_1") (pintype "unspecified"))
    )
    (net (code "42") (name "Net-(U29-FB)") (class "Default")
      (node (ref "R49") (pin "1") (pinfunction "1_1") (pintype "input"))
      (node (ref "R50") (pin "2") (pinfunction "2_2") (pintype "input"))
      (node (ref "U29") (pin "5") (pinfunction "FB_5") (pintype "unspecified"))
    )
    (net (code "43") (name "Net-(U29-GND)") (class "Default")
      (node (ref "C59") (pin "2") (pinfunction "2_2") (pintype "input"))
      (node (ref "C60") (pin "2") (pinfunction "2_2") (pintype "input"))
      (node (ref "C61") (pin "2") (pinfunction "2_2") (pintype "input"))
      (node (ref "C62") (pin "2") (pinfunction "2_2") (pintype "input"))
      (node (ref "R50") (pin "1") (pinfunction "1_1") (pintype "input"))
      (node (ref "R52") (pin "2") (pinfunction "2_2") (pintype "input"))
      (node (ref "U29") (pin "1") (pinfunction "GND_1") (pintype "unspecified"))
    )
    (net (code "44") (name "Net-(U29-SW)") (class "Default")
      (node (ref "D2") (pin "1") (pinfunction "A_1") (pintype "unspecified"))
      (node (ref "D2") (pin "3") (pinfunction "A_3") (pintype "unspecified"))
      (node (ref "L2") (pin "1") (pinfunction "1_1") (pintype "unspecified"))
      (node (ref "U29") (pin "3") (pinfunction "SW_3") (pintype "unspecified"))
    )
    (net (code "45") (name "Net-(U31-Vcp)") (class "Default")
      (node (ref "C64") (pin "1") (pinfunction "1_1") (pintype "input"))
      (node (ref "U31") (pin "17") (pinfunction "Vcp_17") (pintype "unspecified"))
    )
    (net (code "46") (name "Net-(U31-Vref)") (class "Default")
      (node (ref "C65") (pin "1") (pinfunction "1_1") (pintype "input"))
      (node (ref "U31") (pin "16") (pinfunction "Vref_16") (pintype "unspecified"))
    )
    (net (code "47") (name "OUT1") (class "Default")
      (node (ref "H13") (pin "3") (pinfunction "3_3") (pintype "unspecified"))
      (node (ref "U31") (pin "6") (pinfunction "OUT1_6") (pintype "unspecified"))
    )
    (net (code "48") (name "OUT2") (class "Default")
      (node (ref "H13") (pin "2") (pinfunction "2_2") (pintype "unspecified"))
      (node (ref "U31") (pin "5") (pinfunction "OUT2_5") (pintype "unspecified"))
    )
    (net (code "49") (name "OUT3") (class "Default")
      (node (ref "H13") (pin "1") (pinfunction "1_1") (pintype "unspecified"))
      (node (ref "U31") (pin "15") (pinfunction "OUT3_15") (pintype "unspecified"))
    )
    (net (code "50") (name "PA4") (class "Default")
      (node (ref "U27") (pin "2") (pinfunction "2_2") (pintype "unspecified"))
      (node (ref "U5") (pin "29") (pinfunction "PA4_29") (pintype "bidirectional"))
    )
    (net (code "51") (name "PA5") (class "Default")
      (node (ref "U27") (pin "4") (pinfunction "4_4") (pintype "unspecified"))
      (node (ref "U5") (pin "30") (pinfunction "PA5_30") (pintype "bidirectional"))
    )
    (net (code "52") (name "PA6") (class "Default")
      (node (ref "U27") (pin "6") (pinfunction "6_6") (pintype "unspecified"))
      (node (ref "U5") (pin "31") (pinfunction "PA6_31") (pintype "bidirectional"))
    )
    (net (code "53") (name "PA7") (class "Default")
      (node (ref "U27") (pin "8") (pinfunction "8_8") (pintype "unspecified"))
      (node (ref "U5") (pin "32") (pinfunction "PA7_32") (pintype "bidirectional"))
    )
    (net (code "54") (name "PB0") (class "Default")
      (node (ref "U27") (pin "14") (pinfunction "14_14") (pintype "unspecified"))
      (node (ref "U5") (pin "35") (pinfunction "PB0_35") (pintype "bidirectional"))
    )
    (net (code "55") (name "PB1") (class "Default")
      (node (ref "U27") (pin "16") (pinfunction "16_16") (pintype "unspecified"))
      (node (ref "U5") (pin "36") (pinfunction "PB1_36") (pintype "bidirectional"))
    )
    (net (code "56") (name "PC4") (class "Default")
      (node (ref "U27") (pin "10") (pinfunction "10_10") (pintype "unspecified"))
      (node (ref "U5") (pin "33") (pinfunction "PC4_33") (pintype "bidirectional"))
    )
    (net (code "57") (name "PC5") (class "Default")
      (node (ref "U27") (pin "12") (pinfunction "12_12") (pintype "unspecified"))
      (node (ref "U5") (pin "34") (pinfunction "PC5_34") (pintype "bidirectional"))
    )
    (net (code "58") (name "PE8") (class "Default")
      (node (ref "U27") (pin "18") (pinfunction "18_18") (pintype "unspecified"))
      (node (ref "U5") (pin "39") (pinfunction "PE8_39") (pintype "bidirectional"))
    )
    (net (code "59") (name "PE9") (class "Default")
      (node (ref "U27") (pin "20") (pinfunction "20_20") (pintype "unspecified"))
      (node (ref "U5") (pin "40") (pinfunction "PE9_40") (pintype "bidirectional"))
    )
    (net (code "60") (name "PE10") (class "Default")
      (node (ref "U27") (pin "22") (pinfunction "22_22") (pintype "unspecified"))
      (node (ref "U5") (pin "41") (pinfunction "PE10_41") (pintype "bidirectional"))
    )
    (net (code "61") (name "PE11") (class "Default")
      (node (ref "U27") (pin "24") (pinfunction "24_24") (pintype "unspecified"))
      (node (ref "U5") (pin "42") (pinfunction "PE11_42") (pintype "bidirectional"))
    )
    (net (code "62") (name "PE12") (class "Default")
      (node (ref "U27") (pin "23") (pinfunction "23_23") (pintype "unspecified"))
      (node (ref "U5") (pin "43") (pinfunction "PE12_43") (pintype "bidirectional"))
    )
    (net (code "63") (name "PE13") (class "Default")
      (node (ref "U27") (pin "21") (pinfunction "21_21") (pintype "unspecified"))
      (node (ref "U5") (pin "44") (pinfunction "PE13_44") (pintype "bidirectional"))
    )
    (net (code "64") (name "PE14") (class "Default")
      (node (ref "U27") (pin "19") (pinfunction "19_19") (pintype "unspecified"))
      (node (ref "U5") (pin "45") (pinfunction "PE14_45") (pintype "bidirectional"))
    )
    (net (code "65") (name "PE15") (class "Default")
      (node (ref "U27") (pin "17") (pinfunction "17_17") (pintype "unspecified"))
      (node (ref "U5") (pin "46") (pinfunction "PE15_46") (pintype "bidirectional"))
    )
    (net (code "66") (name "PH0-OSC_IN") (class "Default")
      (node (ref "C18") (pin "2") (pinfunction "2_2") (pintype "input"))
      (node (ref "U5") (pin "12") (pinfunction "PH0-OSC_IN(PH0)_12") (pintype "bidirectional"))
      (node (ref "X2") (pin "3") (pinfunction "OSC2_3") (pintype "unspecified"))
    )
    (net (code "67") (name "PH1-OSC_OUT") (class "Default")
      (node (ref "C19") (pin "1") (pinfunction "1_1") (pintype "input"))
      (node (ref "U5") (pin "13") (pinfunction "PH1-OSC_OUT(PH1)_13") (pintype "bidirectional"))
      (node (ref "X2") (pin "1") (pinfunction "OSC1_1") (pintype "unspecified"))
    )
    (net (code "68") (name "RES1") (class "Default")
      (node (ref "R30") (pin "1") (pinfunction "1_1") (pintype "input"))
      (node (ref "U16") (pin "16") (pinfunction "RESET#_16") (pintype "unspecified"))
    )
    (net (code "69") (name "SLP1") (class "Default")
      (node (ref "R29") (pin "1") (pinfunction "1_1") (pintype "input"))
      (node (ref "U16") (pin "17") (pinfunction "SLEEP#_17") (pintype "unspecified"))
    )
    (net (code "70") (name "TIM3_PWM_CH1") (class "Default")
      (node (ref "U16") (pin "27") (pinfunction "IN1_27") (pintype "unspecified"))
      (node (ref "U5") (pin "63") (pinfunction "PC6_63") (pintype "bidirectional"))
    )
    (net (code "71") (name "TIM3_PWM_CH2") (class "Default")
      (node (ref "U16") (pin "25") (pinfunction "IN2_25") (pintype "unspecified"))
      (node (ref "U5") (pin "64") (pinfunction "PC7_64") (pintype "bidirectional"))
    )
    (net (code "72") (name "TIM3_PWM_CH3") (class "Default")
      (node (ref "U16") (pin "23") (pinfunction "IN3_23") (pintype "unspecified"))
      (node (ref "U5") (pin "65") (pinfunction "PC8_65") (pintype "bidirectional"))
    )
    (net (code "73") (name "TIM4_PWM_CH1") (class "Default")
      (node (ref "U31") (pin "14") (pinfunction "IN3_14") (pintype "unspecified"))
      (node (ref "U5") (pin "59") (pinfunction "PD12_59") (pintype "bidirectional"))
    )
    (net (code "74") (name "TIM4_PWM_CH2") (class "Default")
      (node (ref "U31") (pin "7") (pinfunction "IN1_7") (pintype "unspecified"))
      (node (ref "U5") (pin "60") (pinfunction "PD13_60") (pintype "bidirectional"))
    )
    (net (code "75") (name "TIM4_PWM_CH3") (class "Default")
      (node (ref "U31") (pin "4") (pinfunction "IN2_4") (pintype "unspecified"))
      (node (ref "U5") (pin "61") (pinfunction "PD14_61") (pintype "bidirectional"))
    )
    (net (code "76") (name "UART1_RX") (class "Default")
      (node (ref "U5") (pin "69") (pinfunction "PA10_69") (pintype "bidirectional"))
      (node (ref "UART1") (pin "2") (pinfunction "2_2") (pintype "unspecified"))
    )
    (net (code "77") (name "UART1_TX") (class "Default")
      (node (ref "U5") (pin "68") (pinfunction "PA9_68") (pintype "bidirectional"))
      (node (ref "UART1") (pin "3") (pinfunction "3_3") (pintype "unspecified"))
    )
    (net (code "78") (name "UART2_RX") (class "Default")
      (node (ref "H10") (pin "3") (pinfunction "3_3") (pintype "unspecified"))
      (node (ref "JY60") (pin "3") (pinfunction "TX_3") (pintype "input"))
      (node (ref "U5") (pin "26") (pinfunction "PA3_26") (pintype "bidirectional"))
    )
    (net (code "79") (name "UART2_TX") (class "Default")
      (node (ref "H10") (pin "2") (pinfunction "2_2") (pintype "unspecified"))
      (node (ref "JY60") (pin "2") (pinfunction "RX_2") (pintype "input"))
      (node (ref "U5") (pin "25") (pinfunction "PA2_25") (pintype "bidirectional"))
    )
    (net (code "80") (name "UART4_RX") (class "Default")
      (node (ref "U5") (pin "24") (pinfunction "PA1_24") (pintype "bidirectional"))
      (node (ref "UART4") (pin "2") (pinfunction "2_2") (pintype "unspecified"))
    )
    (net (code "81") (name "UART4_TX") (class "Default")
      (node (ref "U5") (pin "23") (pinfunction "PA0-WKUP(PA0)_23") (pintype "bidirectional"))
      (node (ref "UART4") (pin "3") (pinfunction "3_3") (pintype "unspecified"))
    )
    (net (code "82") (name "UART5_RX") (class "Default")
      (node (ref "U5") (pin "83") (pinfunction "PD2_83") (pintype "bidirectional"))
      (node (ref "UART5") (pin "2") (pinfunction "2_2") (pintype "unspecified"))
    )
    (net (code "83") (name "UART5_TX") (class "Default")
      (node (ref "U5") (pin "80") (pinfunction "PC12_80") (pintype "bidirectional"))
      (node (ref "UART5") (pin "3") (pinfunction "3_3") (pintype "unspecified"))
    )
    (net (code "84") (name "VIN") (class "Default")
      (node (ref "C63") (pin "2") (pinfunction "2_2") (pintype "input"))
      (node (ref "C66") (pin "1") (pinfunction "1_1") (pintype "input"))
      (node (ref "C67") (pin "2") (pinfunction "2_2") (pintype "input"))
      (node (ref "D3") (pin "1") (pinfunction "A_1") (pintype "unspecified"))
      (node (ref "H12") (pin "2") (pinfunction "2_2") (pintype "unspecified"))
      (node (ref "U31") (pin "12") (pinfunction "Vs_12") (pintype "unspecified"))
      (node (ref "U31") (pin "9") (pinfunction "Vs_9") (pintype "unspecified"))
    )
    (net (code "85") (name "unconnected-(SCREW1-Pad1)") (class "Default")
      (node (ref "SCREW1") (pin "1") (pinfunction "1_1") (pintype "input+no_connect"))
    )
    (net (code "86") (name "unconnected-(SCREW2-Pad1)") (class "Default")
      (node (ref "SCREW2") (pin "1") (pinfunction "1_1") (pintype "input+no_connect"))
    )
    (net (code "87") (name "unconnected-(SCREW3-Pad1)") (class "Default")
      (node (ref "SCREW3") (pin "1") (pinfunction "1_1") (pintype "input+no_connect"))
    )
    (net (code "88") (name "unconnected-(SCREW4-Pad1)") (class "Default")
      (node (ref "SCREW4") (pin "1") (pinfunction "1_1") (pintype "input+no_connect"))
    )
    (net (code "89") (name "unconnected-(SCREW9-Pad1)") (class "Default")
      (node (ref "SCREW9") (pin "1") (pinfunction "1_1") (pintype "input+no_connect"))
    )
    (net (code "90") (name "unconnected-(SCREW10-Pad1)") (class "Default")
      (node (ref "SCREW10") (pin "1") (pinfunction "1_1") (pintype "input+no_connect"))
    )
    (net (code "91") (name "unconnected-(SCREW11-Pad1)") (class "Default")
      (node (ref "SCREW11") (pin "1") (pinfunction "1_1") (pintype "input+no_connect"))
    )
    (net (code "92") (name "unconnected-(SCREW12-Pad1)") (class "Default")
      (node (ref "SCREW12") (pin "1") (pinfunction "1_1") (pintype "input+no_connect"))
    )
    (net (code "93") (name "unconnected-(SW4-Pad3)") (class "Default")
      (node (ref "SW4") (pin "3") (pinfunction "3_3") (pintype "unspecified"))
    )
    (net (code "94") (name "unconnected-(SW4-Pad4)") (class "Default")
      (node (ref "SW4") (pin "4") (pinfunction "4_4") (pintype "unspecified"))
    )
    (net (code "95") (name "unconnected-(SW4-Pad5)") (class "Default")
      (node (ref "SW4") (pin "5") (pinfunction "5_5") (pintype "unspecified"))
    )
    (net (code "96") (name "unconnected-(U5A-PA11-Pad70)") (class "Default")
      (node (ref "U5") (pin "70") (pinfunction "PA11_70") (pintype "bidirectional"))
    )
    (net (code "97") (name "unconnected-(U5A-PA12-Pad71)") (class "Default")
      (node (ref "U5") (pin "71") (pinfunction "PA12_71") (pintype "bidirectional"))
    )
    (net (code "98") (name "unconnected-(U5A-PA15(JTDI)-Pad77)") (class "Default")
      (node (ref "U5") (pin "77") (pinfunction "PA15(JTDI)_77") (pintype "bidirectional"))
    )
    (net (code "99") (name "unconnected-(U5A-PB3(JTDOTRACESWO)-Pad89)") (class "Default")
      (node (ref "U5") (pin "89") (pinfunction "PB3(JTDOTRACESWO)_89") (pintype "bidirectional"))
    )
    (net (code "100") (name "unconnected-(U5A-PB4(NJTRST)-Pad90)") (class "Default")
      (node (ref "U5") (pin "90") (pinfunction "PB4(NJTRST)_90") (pintype "bidirectional"))
    )
    (net (code "101") (name "unconnected-(U5A-PB5-Pad91)") (class "Default")
      (node (ref "U5") (pin "91") (pinfunction "PB5_91") (pintype "bidirectional"))
    )
    (net (code "102") (name "unconnected-(U5A-PB8-Pad95)") (class "Default")
      (node (ref "U5") (pin "95") (pinfunction "PB8_95") (pintype "bidirectional"))
    )
    (net (code "103") (name "unconnected-(U5A-PB9-Pad96)") (class "Default")
      (node (ref "U5") (pin "96") (pinfunction "PB9_96") (pintype "bidirectional"))
    )
    (net (code "104") (name "unconnected-(U5A-PB13-Pad52)") (class "Default")
      (node (ref "U5") (pin "52") (pinfunction "PB13_52") (pintype "bidirectional"))
    )
    (net (code "105") (name "unconnected-(U5A-PB14-Pad53)") (class "Default")
      (node (ref "U5") (pin "53") (pinfunction "PB14_53") (pintype "bidirectional"))
    )
    (net (code "106") (name "unconnected-(U5A-PB15-Pad54)") (class "Default")
      (node (ref "U5") (pin "54") (pinfunction "PB15_54") (pintype "bidirectional"))
    )
    (net (code "107") (name "unconnected-(U5A-PC0-Pad15)") (class "Default")
      (node (ref "U5") (pin "15") (pinfunction "PC0_15") (pintype "bidirectional"))
    )
    (net (code "108") (name "unconnected-(U5A-PC10-Pad78)") (class "Default")
      (node (ref "U5") (pin "78") (pinfunction "PC10_78") (pintype "bidirectional"))
    )
    (net (code "109") (name "unconnected-(U5A-PC11-Pad79)") (class "Default")
      (node (ref "U5") (pin "79") (pinfunction "PC11_79") (pintype "bidirectional"))
    )
    (net (code "110") (name "unconnected-(U5A-PC13-Pad7)") (class "Default")
      (node (ref "U5") (pin "7") (pinfunction "PC13_7") (pintype "bidirectional"))
    )
    (net (code "111") (name "unconnected-(U5A-PC14-OSC32_IN(PC14)-Pad8)") (class "Default")
      (node (ref "U5") (pin "8") (pinfunction "PC14-OSC32_IN(PC14)_8") (pintype "bidirectional"))
    )
    (net (code "112") (name "unconnected-(U5A-PC15-OSC32_OUT(PC15)-Pad9)") (class "Default")
      (node (ref "U5") (pin "9") (pinfunction "PC15-OSC32_OUT(PC15)_9") (pintype "bidirectional"))
    )
    (net (code "113") (name "unconnected-(U5A-PD0-Pad81)") (class "Default")
      (node (ref "U5") (pin "81") (pinfunction "PD0_81") (pintype "bidirectional"))
    )
    (net (code "114") (name "unconnected-(U5A-PD1-Pad82)") (class "Default")
      (node (ref "U5") (pin "82") (pinfunction "PD1_82") (pintype "bidirectional"))
    )
    (net (code "115") (name "unconnected-(U5A-PD3-Pad84)") (class "Default")
      (node (ref "U5") (pin "84") (pinfunction "PD3_84") (pintype "bidirectional"))
    )
    (net (code "116") (name "unconnected-(U5A-PD4-Pad85)") (class "Default")
      (node (ref "U5") (pin "85") (pinfunction "PD4_85") (pintype "bidirectional"))
    )
    (net (code "117") (name "unconnected-(U5A-PD5-Pad86)") (class "Default")
      (node (ref "U5") (pin "86") (pinfunction "PD5_86") (pintype "bidirectional"))
    )
    (net (code "118") (name "unconnected-(U5A-PD6-Pad87)") (class "Default")
      (node (ref "U5") (pin "87") (pinfunction "PD6_87") (pintype "bidirectional"))
    )
    (net (code "119") (name "unconnected-(U5A-PD7-Pad88)") (class "Default")
      (node (ref "U5") (pin "88") (pinfunction "PD7_88") (pintype "bidirectional"))
    )
    (net (code "120") (name "unconnected-(U5A-PD8-Pad55)") (class "Default")
      (node (ref "U5") (pin "55") (pinfunction "PD8_55") (pintype "bidirectional"))
    )
    (net (code "121") (name "unconnected-(U5A-PD9-Pad56)") (class "Default")
      (node (ref "U5") (pin "56") (pinfunction "PD9_56") (pintype "bidirectional"))
    )
    (net (code "122") (name "unconnected-(U5A-PD10-Pad57)") (class "Default")
      (node (ref "U5") (pin "57") (pinfunction "PD10_57") (pintype "bidirectional"))
    )
    (net (code "123") (name "unconnected-(U5A-PD11-Pad58)") (class "Default")
      (node (ref "U5") (pin "58") (pinfunction "PD11_58") (pintype "bidirectional"))
    )
    (net (code "124") (name "unconnected-(U5A-PD15-Pad62)") (class "Default")
      (node (ref "U5") (pin "62") (pinfunction "PD15_62") (pintype "bidirectional"))
    )
    (net (code "125") (name "unconnected-(U5A-PE0-Pad97)") (class "Default")
      (node (ref "U5") (pin "97") (pinfunction "PE0_97") (pintype "bidirectional"))
    )
    (net (code "126") (name "unconnected-(U5A-PE1-Pad98)") (class "Default")
      (node (ref "U5") (pin "98") (pinfunction "PE1_98") (pintype "bidirectional"))
    )
    (net (code "127") (name "unconnected-(U5A-PE2-Pad1)") (class "Default")
      (node (ref "U5") (pin "1") (pinfunction "PE2_1") (pintype "bidirectional"))
    )
    (net (code "128") (name "unconnected-(U5A-PE3-Pad2)") (class "Default")
      (node (ref "U5") (pin "2") (pinfunction "PE3_2") (pintype "bidirectional"))
    )
    (net (code "129") (name "unconnected-(U5A-PE4-Pad3)") (class "Default")
      (node (ref "U5") (pin "3") (pinfunction "PE4_3") (pintype "bidirectional"))
    )
    (net (code "130") (name "unconnected-(U5A-PE5-Pad4)") (class "Default")
      (node (ref "U5") (pin "4") (pinfunction "PE5_4") (pintype "bidirectional"))
    )
    (net (code "131") (name "unconnected-(U5A-PE6-Pad5)") (class "Default")
      (node (ref "U5") (pin "5") (pinfunction "PE6_5") (pintype "bidirectional"))
    )
    (net (code "132") (name "unconnected-(U5A-PE7-Pad38)") (class "Default")
      (node (ref "U5") (pin "38") (pinfunction "PE7_38") (pintype "bidirectional"))
    )
    (net (code "133") (name "unconnected-(U13-NC-Pad5)") (class "Default")
      (node (ref "U13") (pin "5") (pinfunction "NC_5") (pintype "unspecified"))
    )
    (net (code "134") (name "unconnected-(U16-COMPO#-Pad19)") (class "Default")
      (node (ref "U16") (pin "19") (pinfunction "COMPO#_19") (pintype "unspecified"))
    )
    (net (code "135") (name "unconnected-(U16-NC-Pad21)") (class "Default")
      (node (ref "U16") (pin "21") (pinfunction "NC_21") (pintype "unspecified"))
    )
    (net (code "136") (name "unconnected-(U23-EN-Pad5)") (class "Default")
      (node (ref "U23") (pin "5") (pinfunction "EN_5") (pintype "unspecified"))
    )
    (net (code "137") (name "unconnected-(U23-NC-Pad2)") (class "Default")
      (node (ref "U23") (pin "2") (pinfunction "NC_2") (pintype "unspecified"))
    )
    (net (code "138") (name "unconnected-(U23-NC-Pad3)") (class "Default")
      (node (ref "U23") (pin "3") (pinfunction "NC_3") (pintype "unspecified"))
    )
    (net (code "139") (name "unconnected-(U24-OUT-Pad3)") (class "Default")
      (node (ref "U24") (pin "3") (pinfunction "OUT_3") (pintype "unspecified+no_connect"))
    )
    (net (code "140") (name "unconnected-(U24-PUSH-Pad5)") (class "Default")
      (node (ref "U24") (pin "5") (pinfunction "PUSH_5") (pintype "unspecified+no_connect"))
    )
    (net (code "141") (name "unconnected-(U24-Z-Pad8)") (class "Default")
      (node (ref "U24") (pin "8") (pinfunction "Z_8") (pintype "unspecified+no_connect"))
    )
    (net (code "142") (name "unconnected-(U26-Pad4)") (class "Default")
      (node (ref "U26") (pin "4") (pinfunction "4_4") (pintype "unspecified+no_connect"))
    )
    (net (code "143") (name "unconnected-(U26-Pad5)") (class "Default")
      (node (ref "U26") (pin "5") (pinfunction "5_5") (pintype "unspecified+no_connect"))
    )
    (net (code "144") (name "unconnected-(U28-Pad4)") (class "Default")
      (node (ref "U28") (pin "4") (pinfunction "4_4") (pintype "unspecified+no_connect"))
    )
    (net (code "145") (name "unconnected-(U28-Pad6)") (class "Default")
      (node (ref "U28") (pin "6") (pinfunction "6_6") (pintype "unspecified"))
    )
    (net (code "146") (name "unconnected-(U28-Pad7)") (class "Default")
      (node (ref "U28") (pin "7") (pinfunction "7_7") (pintype "unspecified"))
    )
    (net (code "147") (name "unconnected-(U29-EN-Pad2)") (class "Default")
      (node (ref "U29") (pin "2") (pinfunction "EN_2") (pintype "unspecified"))
    )
    (net (code "148") (name "unconnected-(UART1-Pad5)") (class "Default")
      (node (ref "UART1") (pin "5") (pinfunction "5_5") (pintype "unspecified"))
    )
    (net (code "149") (name "unconnected-(UART1-Pad6)") (class "Default")
      (node (ref "UART1") (pin "6") (pinfunction "6_6") (pintype "unspecified"))
    )
    (net (code "150") (name "unconnected-(UART4-Pad5)") (class "Default")
      (node (ref "UART4") (pin "5") (pinfunction "5_5") (pintype "unspecified"))
    )
    (net (code "151") (name "unconnected-(UART4-Pad6)") (class "Default")
      (node (ref "UART4") (pin "6") (pinfunction "6_6") (pintype "unspecified"))
    )
    (net (code "152") (name "unconnected-(UART5-Pad5)") (class "Default")
      (node (ref "UART5") (pin "5") (pinfunction "5_5") (pintype "unspecified"))
    )
    (net (code "153") (name "unconnected-(UART5-Pad6)") (class "Default")
      (node (ref "UART5") (pin "6") (pinfunction "6_6") (pintype "unspecified"))
    )
  )
)
